# Touch_Sensing.net
KiCad netlist of a schematic drawn in Altium Designer
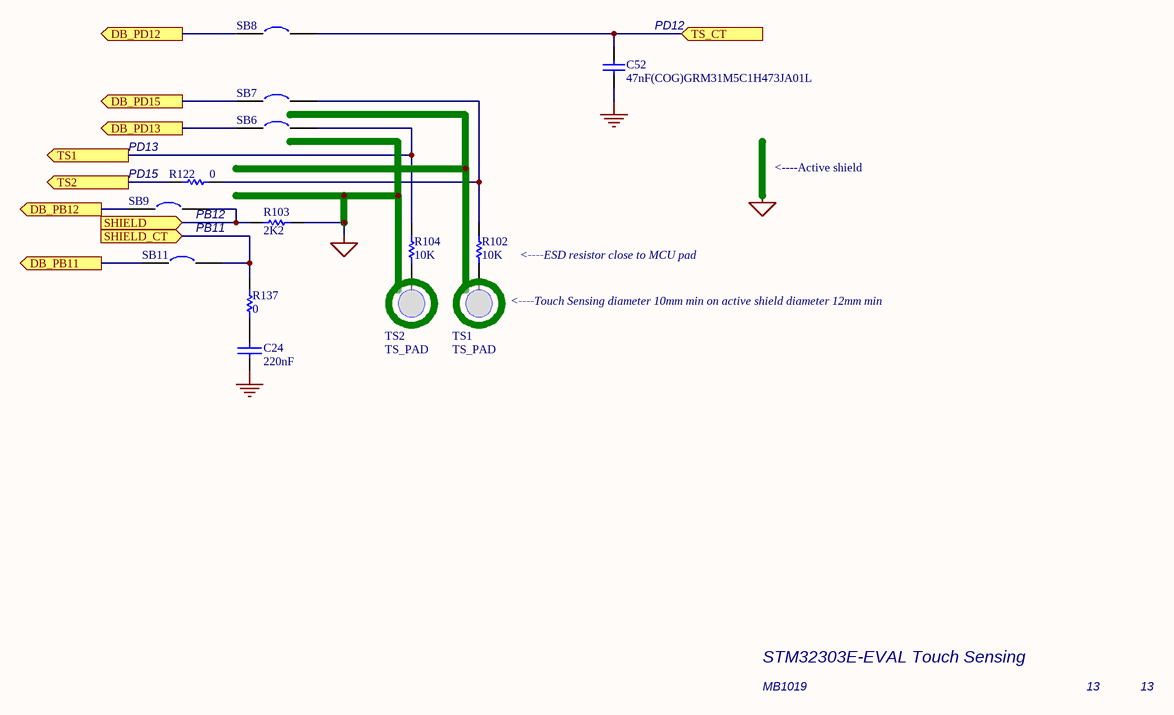
[diagram p0: Touch Sensing.SchDoc]

(export (version "E")
  (design (tool "Eeschema 10.0.6"))
  (components
    (comp (ref "C24")
      (value "220nF")
      (footprint "0603C")
      (description "Capacitor")
      (libsource (lib "*") (part "CAP"))
    )
    (comp (ref "C52")
      (value "47nF(COG)GRM31M5C1H473JA01L")
      (footprint "1206C")
      (description "Capacitor")
      (fields (field (name "PUBLISHER") "Altium Limited"))
      (libsource (lib "Miscellaneous Devices") (part "CAP"))
    )
    (comp (ref "R102")
      (value "10K")
      (footprint "0603R")
      (description "Resistor")
      (fields (field (name "PUBLISHER") "Altium Limited"))
      (libsource (lib "Miscellaneous Devices") (part "Res1"))
    )
    (comp (ref "R103")
      (value "2K2")
      (footprint "0603R")
      (description "Resistor")
      (fields (field (name "PUBLISHER") "Altium Limited"))
      (libsource (lib "Miscellaneous Devices") (part "Res1"))
    )
    (comp (ref "R104")
      (value "10K")
      (footprint "0603R")
      (description "Resistor")
      (fields (field (name "PUBLISHER") "Altium Limited"))
      (libsource (lib "Miscellaneous Devices") (part "Res1"))
    )
    (comp (ref "R122")
      (value "0")
      (footprint "0603R")
      (description "Resistor")
      (fields (field (name "PUBLISHER") "Altium Limited"))
      (libsource (lib "Miscellaneous Devices") (part "Res1"))
    )
    (comp (ref "R137")
      (value "0")
      (footprint "0603R")
      (description "Resistor")
      (fields (field (name "PUBLISHER") "Altium Limited"))
      (libsource (lib "Miscellaneous Devices") (part "Res1"))
    )
    (comp (ref "SB6")
      (value "~")
      (footprint "JP2_SMD")
      (description "Circuit Breaker")
      (fields (field (name "PUBLISHER") "Altium Limited"))
      (libsource (lib "Miscellaneous Devices") (part "Circuit Breaker"))
    )
    (comp (ref "SB7")
      (value "~")
      (footprint "JP2_SMD")
      (description "Circuit Breaker")
      (fields (field (name "PUBLISHER") "Altium Limited"))
      (libsource (lib "Miscellaneous Devices") (part "Circuit Breaker"))
    )
    (comp (ref "SB8")
      (value "~")
      (footprint "JP2_SMD")
      (description "Circuit Breaker")
      (fields (field (name "PUBLISHER") "Altium Limited"))
      (libsource (lib "Miscellaneous Devices") (part "Circuit Breaker"))
    )
    (comp (ref "SB9")
      (value "~")
      (footprint "JP2_SMD")
      (description "Circuit Breaker")
      (fields (field (name "PUBLISHER") "Altium Limited"))
      (libsource (lib "Miscellaneous Devices") (part "Circuit Breaker"))
    )
    (comp (ref "SB11")
      (value "~")
      (footprint "JP2_SMD")
      (description "Circuit Breaker")
      (fields (field (name "PUBLISHER") "Altium Limited"))
      (libsource (lib "Miscellaneous Devices") (part "Circuit Breaker"))
    )
    (comp (ref "TS1") (value "TS_PAD") (footprint "TS_PAD") (libsource (lib "MB819") (part "TS_PAD")))
    (comp (ref "TS2") (value "TS_PAD") (footprint "TS_PAD") (libsource (lib "MB819") (part "TS_PAD")))
  )
  (nets
    (net (code "1") (name "/DB_PB11") (class "Default")
      (node (ref "SB11") (pin "1") (pinfunction "1_1") (pintype "passive"))
    )
    (net (code "2") (name "/DB_PB12") (class "Default")
      (node (ref "SB9") (pin "1") (pinfunction "1_1") (pintype "passive"))
    )
    (net (code "3") (name "/DB_PD12") (class "Default")
      (node (ref "SB8") (pin "1") (pinfunction "1_1") (pintype "passive"))
    )
    (net (code "4") (name "/DB_PD13") (class "Default")
      (node (ref "SB6") (pin "1") (pinfunction "1_1") (pintype "passive"))
    )
    (net (code "5") (name "/DB_PD15") (class "Default")
      (node (ref "SB7") (pin "1") (pinfunction "1_1") (pintype "passive"))
    )
    (net (code "6") (name "/SHIELD") (class "Default")
      (node (ref "R103") (pin "1") (pinfunction "1_1") (pintype "passive"))
      (node (ref "SB9") (pin "2") (pinfunction "2_2") (pintype "passive"))
    )
    (net (code "7") (name "/SHIELD_CT") (class "Default")
      (node (ref "R137") (pin "1") (pinfunction "1_1") (pintype "passive"))
      (node (ref "SB11") (pin "2") (pinfunction "2_2") (pintype "passive"))
    )
    (net (code "8") (name "/TS1") (class "Default")
      (node (ref "R104") (pin "1") (pinfunction "1_1") (pintype "passive"))
      (node (ref "SB6") (pin "2") (pinfunction "2_2") (pintype "passive"))
    )
    (net (code "9") (name "/TS2") (class "Default")
      (node (ref "R122") (pin "2") (pinfunction "2_2") (pintype "passive"))
    )
    (net (code "10") (name "/TS_CT") (class "Default")
      (node (ref "C52") (pin "2") (pinfunction "2_2") (pintype "passive"))
      (node (ref "SB8") (pin "2") (pinfunction "2_2") (pintype "passive"))
    )
    (net (code "11") (name "GND") (class "Default")
      (node (ref "C24") (pin "1") (pinfunction "1_1") (pintype "passive"))
      (node (ref "C52") (pin "1") (pinfunction "1_1") (pintype "passive"))
    )
    (net (code "12") (name "Net-(C24-Pad2)") (class "Default")
      (node (ref "C24") (pin "2") (pinfunction "2_2") (pintype "passive"))
      (node (ref "R137") (pin "2") (pinfunction "2_2") (pintype "passive"))
    )
    (net (code "13") (name "Net-(R102-Pad1)") (class "Default")
      (node (ref "R102") (pin "1") (pinfunction "1_1") (pintype "passive"))
      (node (ref "R122") (pin "1") (pinfunction "1_1") (pintype "passive"))
      (node (ref "SB7") (pin "2") (pinfunction "2_2") (pintype "passive"))
    )
    (net (code "14") (name "Net-(R102-Pad2)") (class "Default")
      (node (ref "R102") (pin "2") (pinfunction "2_2") (pintype "passive"))
      (node (ref "TS1") (pin "1") (pinfunction "1_1") (pintype "passive"))
    )
    (net (code "15") (name "Net-(R104-Pad2)") (class "Default")
      (node (ref "R104") (pin "2") (pinfunction "2_2") (pintype "passive"))
      (node (ref "TS2") (pin "1") (pinfunction "1_1") (pintype "passive"))
    )
    (net (code "16") (name "TS_SHIELD") (class "Default")
      (node (ref "R103") (pin "2") (pinfunction "2_2") (pintype "passive"))
    )
  )
)
